# LTC6362_Schematic_2.net
KiCad netlist of a schematic drawn in Altium Designer
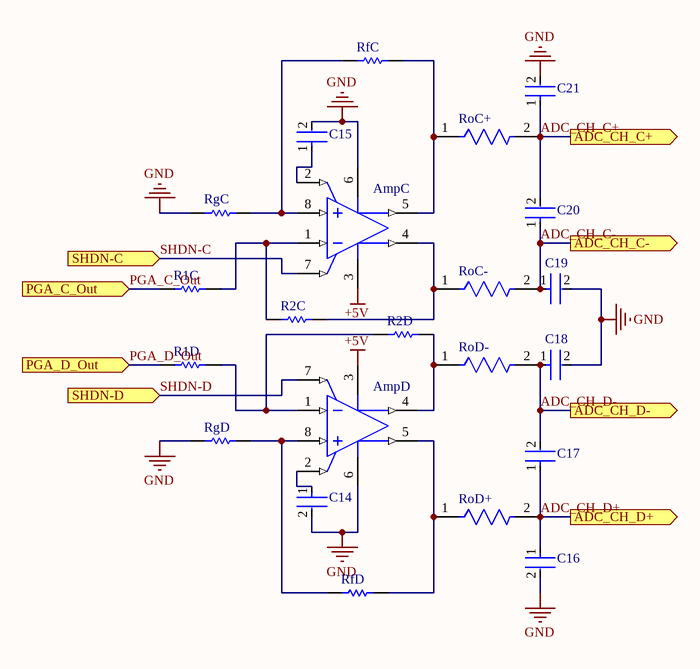
[diagram p0: LTC6362_Schematic_2.SchDoc]

(export (version "E")
  (design (tool "Eeschema 10.0.6"))
  (components
    (comp (ref "AmpC")
      (value "LTC6362HMS8#PBF")
      (footprint "LT-MS8-8_L")
      (fields
        (field (name "LINEAR TECHNOLOGY PART NUMBER") "LTC6362")
        (field (name "MANUFACTURER") "Linear Technology")
      )
      (libsource (lib "LTC6362HMS8_Symbol") (part "CMP-0359-00920-2"))
    )
    (comp (ref "AmpD")
      (value "LTC6362HMS8#PBF")
      (footprint "LT-MS8-8_L")
      (fields
        (field (name "LINEAR TECHNOLOGY PART NUMBER") "LTC6362")
        (field (name "MANUFACTURER") "Linear Technology")
      )
      (libsource (lib "LTC6362HMS8_Symbol") (part "CMP-0359-00920-2"))
    )
    (comp (ref "C14")
      (value "GQM1875C2ER10BB12D")
      (footprint "FP-GQM187-0_15-MFG")
      (description "Ceramic Capacitor 0.1pF ±0.1pF 250VDC C0G 0603 Paper T/R")
      (libsource (lib "Altium Content Vault") (part "02cd4be3c70576c341d710602a673aa"))
    )
    (comp (ref "C15")
      (value "GQM1875C2ER10BB12D")
      (footprint "FP-GQM187-0_15-MFG")
      (description "Ceramic Capacitor 0.1pF ±0.1pF 250VDC C0G 0603 Paper T/R")
      (libsource (lib "Altium Content Vault") (part "02cd4be3c70576c341d710602a673aa"))
    )
    (comp (ref "C16")
      (value "CC0603KRX7R9BB392")
      (footprint "FP-CC0603-DA-MFG")
      (description "CAP CER 3900PF 50V X7R 0603")
      (fields (field (name "TOLERANCE") "10%") (field (name "VOLTAGE") "50V"))
      (libsource (lib "Altium Content Vault") (part "11868f565c42a9108669ba33697ecf6"))
    )
    (comp (ref "C17")
      (value "CC0603KRX7R9BB392")
      (footprint "FP-CC0603-DA-MFG")
      (description "CAP CER 3900PF 50V X7R 0603")
      (fields (field (name "TOLERANCE") "10%") (field (name "VOLTAGE") "50V"))
      (libsource (lib "Altium Content Vault") (part "11868f565c42a9108669ba33697ecf6"))
    )
    (comp (ref "C18")
      (value "CC0603KRX7R9BB392")
      (footprint "FP-CC0603-DA-MFG")
      (description "CAP CER 3900PF 50V X7R 0603")
      (fields (field (name "TOLERANCE") "10%") (field (name "VOLTAGE") "50V"))
      (libsource (lib "Altium Content Vault") (part "11868f565c42a9108669ba33697ecf6"))
    )
    (comp (ref "C19")
      (value "CC0603KRX7R9BB392")
      (footprint "FP-CC0603-DA-MFG")
      (description "CAP CER 3900PF 50V X7R 0603")
      (fields (field (name "TOLERANCE") "10%") (field (name "VOLTAGE") "50V"))
      (libsource (lib "Altium Content Vault") (part "11868f565c42a9108669ba33697ecf6"))
    )
    (comp (ref "C20")
      (value "CC0603KRX7R9BB392")
      (footprint "FP-CC0603-DA-MFG")
      (description "CAP CER 3900PF 50V X7R 0603")
      (fields (field (name "TOLERANCE") "10%") (field (name "VOLTAGE") "50V"))
      (libsource (lib "Altium Content Vault") (part "11868f565c42a9108669ba33697ecf6"))
    )
    (comp (ref "C21")
      (value "CC0603KRX7R9BB392")
      (footprint "FP-CC0603-DA-MFG")
      (description "CAP CER 3900PF 50V X7R 0603")
      (fields (field (name "TOLERANCE") "10%") (field (name "VOLTAGE") "50V"))
      (libsource (lib "Altium Content Vault") (part "11868f565c42a9108669ba33697ecf6"))
    )
    (comp (ref "R1C")
      (value "ERJ-6ENF1241V")
      (footprint "RESC2013X70X40LL20T20")
      (fields (field (name "MANUFACTURER") "Panasonic"))
      (libsource (lib "Altium Content Vault") (part "RES"))
    )
    (comp (ref "R1D")
      (value "ERJ-6ENF1241V")
      (footprint "RESC2013X70X40LL20T20")
      (fields (field (name "MANUFACTURER") "Panasonic"))
      (libsource (lib "Altium Content Vault") (part "RES"))
    )
    (comp (ref "R2C")
      (value "RC0805FR-071KL")
      (footprint "RESC2013X60X35ML10T20")
      (description "Chip Resistor, 1 KOhm, +/- 1%, 125 mW, -55 to 155 degC, 0805 (2012 Metric), RoHS, Tape and Reel")
      (fields (field (name "TOLERANCE") "1%") (field (name "MANUFACTURER") "Yageo"))
      (libsource (lib "Altium Content Vault") (part "RES-2"))
    )
    (comp (ref "R2D")
      (value "RC0805FR-071KL")
      (footprint "RESC2013X60X35ML10T20")
      (description "Chip Resistor, 1 KOhm, +/- 1%, 125 mW, -55 to 155 degC, 0805 (2012 Metric), RoHS, Tape and Reel")
      (fields (field (name "TOLERANCE") "1%") (field (name "MANUFACTURER") "Yageo"))
      (libsource (lib "Altium Content Vault") (part "RES-2"))
    )
    (comp (ref "RfC")
      (value "RC0805FR-071KL")
      (footprint "RESC2013X60X35ML10T20")
      (description "Chip Resistor, 1 KOhm, +/- 1%, 125 mW, -55 to 155 degC, 0805 (2012 Metric), RoHS, Tape and Reel")
      (fields (field (name "TOLERANCE") "1%") (field (name "MANUFACTURER") "Yageo"))
      (libsource (lib "Altium Content Vault") (part "RES-2"))
    )
    (comp (ref "RfD")
      (value "RC0805FR-071KL")
      (footprint "RESC2013X60X35ML10T20")
      (description "Chip Resistor, 1 KOhm, +/- 1%, 125 mW, -55 to 155 degC, 0805 (2012 Metric), RoHS, Tape and Reel")
      (fields (field (name "TOLERANCE") "1%") (field (name "MANUFACTURER") "Yageo"))
      (libsource (lib "Altium Content Vault") (part "RES-2"))
    )
    (comp (ref "RgC")
      (value "ERJ-6ENF1241V")
      (footprint "RESC2013X70X40LL20T20")
      (fields (field (name "MANUFACTURER") "Panasonic"))
      (libsource (lib "Altium Content Vault") (part "RES"))
    )
    (comp (ref "RgD")
      (value "ERJ-6ENF1241V")
      (footprint "RESC2013X70X40LL20T20")
      (fields (field (name "MANUFACTURER") "Panasonic"))
      (libsource (lib "Altium Content Vault") (part "RES"))
    )
    (comp (ref "RoC+")
      (value "CRCW060335K7FKEA")
      (footprint "FP-CRCW0603-e3-IPC_C")
      (description "RES Thick Film, 35.7kΩ, 1%, 0.1W, 100ppm/°C, 0603")
      (fields (field (name "TOLERANCE") "1%"))
      (libsource (lib "Altium Content Vault") (part "1029c3af85768c4190bb7ad29bc67b5"))
    )
    (comp (ref "RoC-")
      (value "CRCW060335K7FKEA")
      (footprint "FP-CRCW0603-e3-IPC_C")
      (description "RES Thick Film, 35.7kΩ, 1%, 0.1W, 100ppm/°C, 0603")
      (fields (field (name "TOLERANCE") "1%"))
      (libsource (lib "Altium Content Vault") (part "1029c3af85768c4190bb7ad29bc67b5"))
    )
    (comp (ref "RoD+")
      (value "CRCW060335K7FKEA")
      (footprint "FP-CRCW0603-e3-IPC_C")
      (description "RES Thick Film, 35.7kΩ, 1%, 0.1W, 100ppm/°C, 0603")
      (fields (field (name "TOLERANCE") "1%"))
      (libsource (lib "Altium Content Vault") (part "1029c3af85768c4190bb7ad29bc67b5"))
    )
    (comp (ref "RoD-")
      (value "CRCW060335K7FKEA")
      (footprint "FP-CRCW0603-e3-IPC_C")
      (description "RES Thick Film, 35.7kΩ, 1%, 0.1W, 100ppm/°C, 0603")
      (fields (field (name "TOLERANCE") "1%"))
      (libsource (lib "Altium Content Vault") (part "1029c3af85768c4190bb7ad29bc67b5"))
    )
  )
  (nets
    (net (code "1") (name "+5V") (class "Default")
      (node (ref "AmpC") (pin "3") (pinfunction "V+_3") (pintype "power_in"))
      (node (ref "AmpD") (pin "3") (pinfunction "V+_3") (pintype "power_in"))
    )
    (net (code "2") (name "/ADC_CH_C+") (class "Default")
      (node (ref "C20") (pin "2") (pinfunction "2_2") (pintype "passive"))
      (node (ref "C21") (pin "1") (pinfunction "1_1") (pintype "passive"))
      (node (ref "RoC+") (pin "2") (pinfunction "2_2") (pintype "passive"))
    )
    (net (code "3") (name "/ADC_CH_C-") (class "Default")
      (node (ref "C19") (pin "1") (pinfunction "1_1") (pintype "passive"))
      (node (ref "C20") (pin "1") (pinfunction "1_1") (pintype "passive"))
      (node (ref "RoC-") (pin "2") (pinfunction "2_2") (pintype "passive"))
    )
    (net (code "4") (name "/ADC_CH_D+") (class "Default")
      (node (ref "C16") (pin "1") (pinfunction "1_1") (pintype "passive"))
      (node (ref "C17") (pin "1") (pinfunction "1_1") (pintype "passive"))
      (node (ref "RoD+") (pin "2") (pinfunction "2_2") (pintype "passive"))
    )
    (net (code "5") (name "/ADC_CH_D-") (class "Default")
      (node (ref "C17") (pin "2") (pinfunction "2_2") (pintype "passive"))
      (node (ref "C18") (pin "1") (pinfunction "1_1") (pintype "passive"))
      (node (ref "RoD-") (pin "2") (pinfunction "2_2") (pintype "passive"))
    )
    (net (code "6") (name "/PGA_C_Out") (class "Default")
      (node (ref "R1C") (pin "1") (pinfunction "1_1") (pintype "passive"))
    )
    (net (code "7") (name "/PGA_D_Out") (class "Default")
      (node (ref "R1D") (pin "1") (pinfunction "1_1") (pintype "passive"))
    )
    (net (code "8") (name "/SHDN-C") (class "Default")
      (node (ref "AmpC") (pin "7") (pinfunction "~{SHDN}_7") (pintype "input"))
    )
    (net (code "9") (name "/SHDN-D") (class "Default")
      (node (ref "AmpD") (pin "7") (pinfunction "~{SHDN}_7") (pintype "input"))
    )
    (net (code "10") (name "GND") (class "Default")
      (node (ref "AmpC") (pin "6") (pinfunction "V-_6") (pintype "power_in"))
      (node (ref "AmpD") (pin "6") (pinfunction "V-_6") (pintype "power_in"))
      (node (ref "C14") (pin "2") (pinfunction "2_2") (pintype "passive"))
      (node (ref "C15") (pin "2") (pinfunction "2_2") (pintype "passive"))
      (node (ref "C16") (pin "2") (pinfunction "2_2") (pintype "passive"))
      (node (ref "C18") (pin "2") (pinfunction "2_2") (pintype "passive"))
      (node (ref "C19") (pin "2") (pinfunction "2_2") (pintype "passive"))
      (node (ref "C21") (pin "2") (pinfunction "2_2") (pintype "passive"))
      (node (ref "RgC") (pin "1") (pinfunction "1_1") (pintype "passive"))
      (node (ref "RgD") (pin "1") (pinfunction "1_1") (pintype "passive"))
    )
    (net (code "11") (name "Net-(AmpC-+IN)") (class "Default")
      (node (ref "AmpC") (pin "8") (pinfunction "+IN_8") (pintype "input"))
      (node (ref "RfC") (pin "1") (pinfunction "1_1") (pintype "passive"))
      (node (ref "RgC") (pin "2") (pinfunction "2_2") (pintype "passive"))
    )
    (net (code "12") (name "Net-(AmpC-+OUT)") (class "Default")
      (node (ref "AmpC") (pin "4") (pinfunction "+OUT_4") (pintype "output"))
      (node (ref "R2C") (pin "2") (pinfunction "2_2") (pintype "passive"))
      (node (ref "RoC-") (pin "1") (pinfunction "1_1") (pintype "passive"))
    )
    (net (code "13") (name "Net-(AmpC--IN)") (class "Default")
      (node (ref "AmpC") (pin "1") (pinfunction "-IN_1") (pintype "input"))
      (node (ref "R1C") (pin "2") (pinfunction "2_2") (pintype "passive"))
      (node (ref "R2C") (pin "1") (pinfunction "1_1") (pintype "passive"))
    )
    (net (code "14") (name "Net-(AmpC--OUT)") (class "Default")
      (node (ref "AmpC") (pin "5") (pinfunction "-OUT_5") (pintype "output"))
      (node (ref "RfC") (pin "2") (pinfunction "2_2") (pintype "passive"))
      (node (ref "RoC+") (pin "1") (pinfunction "1_1") (pintype "passive"))
    )
    (net (code "15") (name "Net-(AmpC-VOCM)") (class "Default")
      (node (ref "AmpC") (pin "2") (pinfunction "VOCM_2") (pintype "input"))
      (node (ref "C15") (pin "1") (pinfunction "1_1") (pintype "passive"))
    )
    (net (code "16") (name "Net-(AmpD-+IN)") (class "Default")
      (node (ref "AmpD") (pin "8") (pinfunction "+IN_8") (pintype "input"))
      (node (ref "RfD") (pin "1") (pinfunction "1_1") (pintype "passive"))
      (node (ref "RgD") (pin "2") (pinfunction "2_2") (pintype "passive"))
    )
    (net (code "17") (name "Net-(AmpD-+OUT)") (class "Default")
      (node (ref "AmpD") (pin "4") (pinfunction "+OUT_4") (pintype "output"))
      (node (ref "R2D") (pin "2") (pinfunction "2_2") (pintype "passive"))
      (node (ref "RoD-") (pin "1") (pinfunction "1_1") (pintype "passive"))
    )
    (net (code "18") (name "Net-(AmpD--IN)") (class "Default")
      (node (ref "AmpD") (pin "1") (pinfunction "-IN_1") (pintype "input"))
      (node (ref "R1D") (pin "2") (pinfunction "2_2") (pintype "passive"))
      (node (ref "R2D") (pin "1") (pinfunction "1_1") (pintype "passive"))
    )
    (net (code "19") (name "Net-(AmpD--OUT)") (class "Default")
      (node (ref "AmpD") (pin "5") (pinfunction "-OUT_5") (pintype "output"))
      (node (ref "RfD") (pin "2") (pinfunction "2_2") (pintype "passive"))
      (node (ref "RoD+") (pin "1") (pinfunction "1_1") (pintype "passive"))
    )
    (net (code "20") (name "Net-(AmpD-VOCM)") (class "Default")
      (node (ref "AmpD") (pin "2") (pinfunction "VOCM_2") (pintype "input"))
      (node (ref "C14") (pin "1") (pinfunction "1_1") (pintype "passive"))
    )
  )
)
